# 07_LMS7002M_Power.net
KiCad netlist of a schematic drawn in Altium Designer
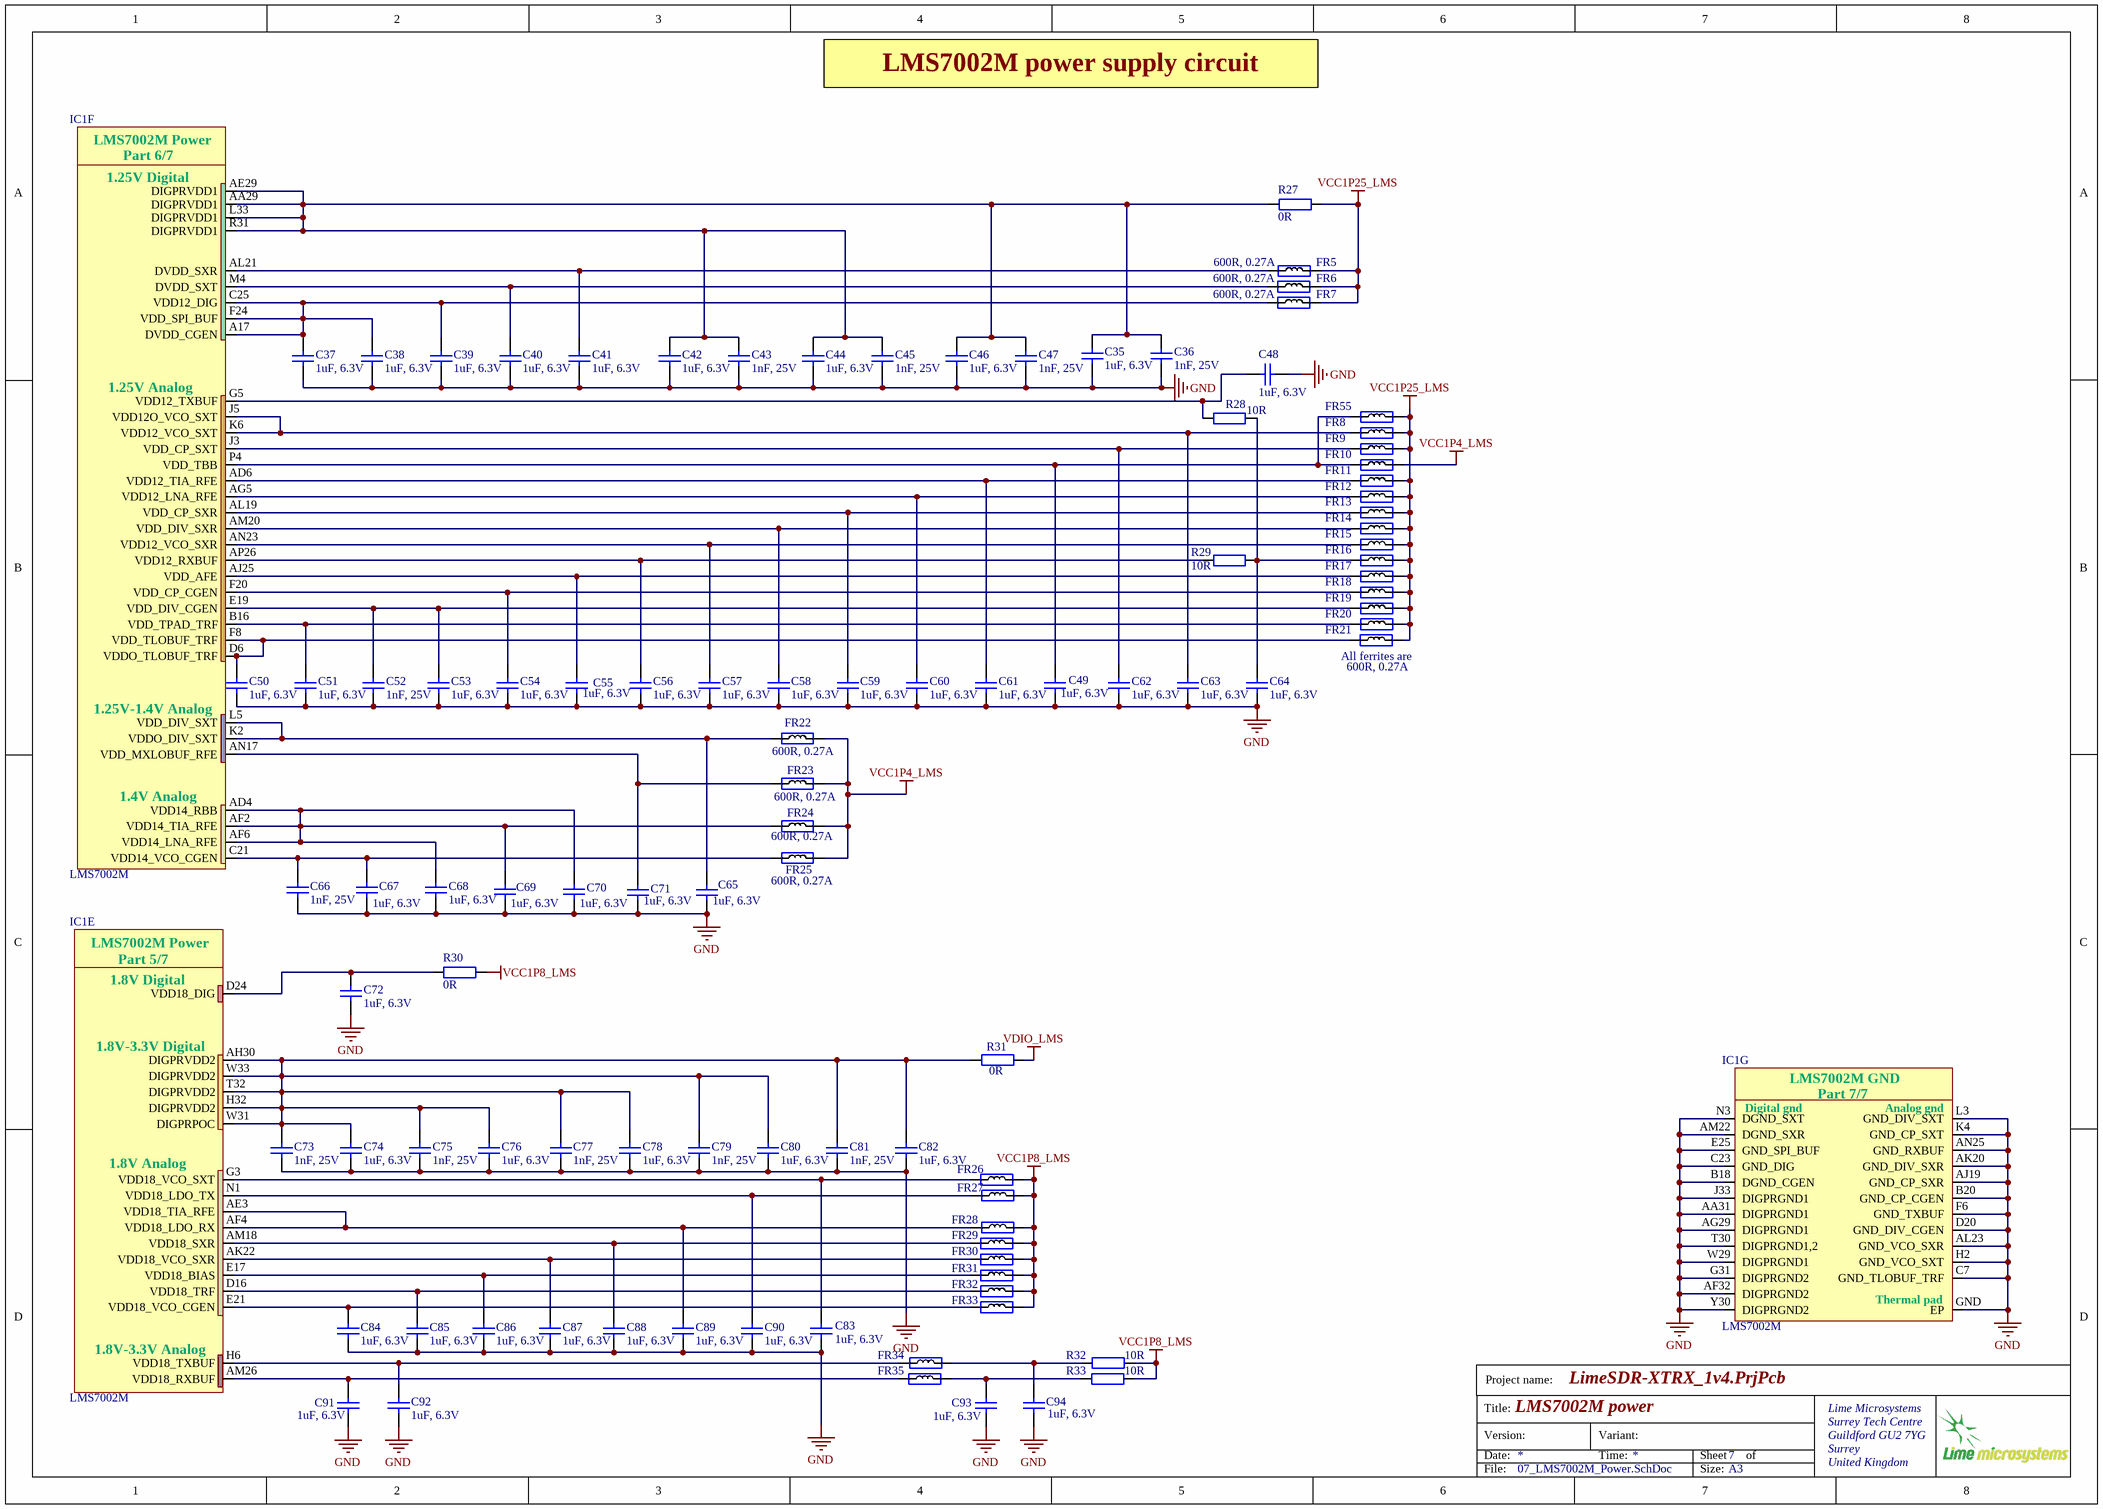
[diagram p0: 07_LMS7002M_Power.SchDoc]

(export (version "E")
  (design (tool "Eeschema 10.0.6"))
  (components
    (comp (ref "C35")
      (value "1uF, 6.3V")
      (footprint "CAP0201")
      (fields (field (name "TOLERANCE") "±20%") (field (name "MANUFACTURER") "TDK Corporation"))
      (libsource (lib "LimeMicroAltiumLib_schLib") (part "Cap_0402"))
    )
    (comp (ref "C36")
      (value "1nF, 25V")
      (footprint "CAP0201")
      (fields (field (name "TOLERANCE") "±10%") (field (name "MANUFACTURER") "TDK Corporation"))
      (libsource (lib "LimeMicroAltiumLib_schLib") (part "Cap_0402"))
    )
    (comp (ref "C37")
      (value "1uF, 6.3V")
      (footprint "CAP0201")
      (fields (field (name "TOLERANCE") "±20%") (field (name "MANUFACTURER") "TDK Corporation"))
      (libsource (lib "LimeMicroAltiumLib_schLib") (part "Cap_0402"))
    )
    (comp (ref "C38")
      (value "1uF, 6.3V")
      (footprint "CAP0201")
      (fields (field (name "TOLERANCE") "±20%") (field (name "MANUFACTURER") "TDK Corporation"))
      (libsource (lib "LimeMicroAltiumLib_schLib") (part "Cap_0402"))
    )
    (comp (ref "C39")
      (value "1uF, 6.3V")
      (footprint "CAP0201")
      (fields (field (name "TOLERANCE") "±20%") (field (name "MANUFACTURER") "TDK Corporation"))
      (libsource (lib "LimeMicroAltiumLib_schLib") (part "Cap_0402"))
    )
    (comp (ref "C40")
      (value "1uF, 6.3V")
      (footprint "CAP0201")
      (fields (field (name "TOLERANCE") "±20%") (field (name "MANUFACTURER") "TDK Corporation"))
      (libsource (lib "LimeMicroAltiumLib_schLib") (part "Cap_0402"))
    )
    (comp (ref "C41")
      (value "1uF, 6.3V")
      (footprint "CAP0201")
      (fields (field (name "TOLERANCE") "±20%") (field (name "MANUFACTURER") "TDK Corporation"))
      (libsource (lib "LimeMicroAltiumLib_schLib") (part "Cap_0402"))
    )
    (comp (ref "C42")
      (value "1uF, 6.3V")
      (footprint "CAP0201")
      (fields (field (name "TOLERANCE") "±20%") (field (name "MANUFACTURER") "TDK Corporation"))
      (libsource (lib "LimeMicroAltiumLib_schLib") (part "Cap_0402"))
    )
    (comp (ref "C43")
      (value "1nF, 25V")
      (footprint "CAP0201")
      (fields (field (name "TOLERANCE") "±10%") (field (name "MANUFACTURER") "TDK Corporation"))
      (libsource (lib "LimeMicroAltiumLib_schLib") (part "Cap_0402"))
    )
    (comp (ref "C44")
      (value "1uF, 6.3V")
      (footprint "CAP0201")
      (fields (field (name "TOLERANCE") "±20%") (field (name "MANUFACTURER") "TDK Corporation"))
      (libsource (lib "LimeMicroAltiumLib_schLib") (part "Cap_0402"))
    )
    (comp (ref "C45")
      (value "1nF, 25V")
      (footprint "CAP0201")
      (fields (field (name "TOLERANCE") "±10%") (field (name "MANUFACTURER") "TDK Corporation"))
      (libsource (lib "LimeMicroAltiumLib_schLib") (part "Cap_0402"))
    )
    (comp (ref "C46")
      (value "1uF, 6.3V")
      (footprint "CAP0201")
      (fields (field (name "TOLERANCE") "±20%") (field (name "MANUFACTURER") "TDK Corporation"))
      (libsource (lib "LimeMicroAltiumLib_schLib") (part "Cap_0402"))
    )
    (comp (ref "C47")
      (value "1nF, 25V")
      (footprint "CAP0201")
      (fields (field (name "TOLERANCE") "±10%") (field (name "MANUFACTURER") "TDK Corporation"))
      (libsource (lib "LimeMicroAltiumLib_schLib") (part "Cap_0402"))
    )
    (comp (ref "C48")
      (value "1uF, 6.3V")
      (footprint "CAP0201")
      (fields (field (name "TOLERANCE") "±20%") (field (name "MANUFACTURER") "TDK Corporation"))
      (libsource (lib "LimeMicroAltiumLib_schLib") (part "Cap_0402"))
    )
    (comp (ref "C49")
      (value "1uF, 6.3V")
      (footprint "CAP0201")
      (fields (field (name "TOLERANCE") "±20%") (field (name "MANUFACTURER") "TDK Corporation"))
      (libsource (lib "LimeMicroAltiumLib_schLib") (part "Cap_0402"))
    )
    (comp (ref "C50")
      (value "1uF, 6.3V")
      (footprint "CAP0201")
      (fields (field (name "TOLERANCE") "±20%") (field (name "MANUFACTURER") "TDK Corporation"))
      (libsource (lib "LimeMicroAltiumLib_schLib") (part "Cap_0402"))
    )
    (comp (ref "C51")
      (value "1uF, 6.3V")
      (footprint "CAP0201")
      (fields (field (name "TOLERANCE") "±20%") (field (name "MANUFACTURER") "TDK Corporation"))
      (libsource (lib "LimeMicroAltiumLib_schLib") (part "Cap_0402"))
    )
    (comp (ref "C52")
      (value "1nF, 25V")
      (footprint "CAP0201")
      (fields (field (name "TOLERANCE") "±10%") (field (name "MANUFACTURER") "TDK Corporation"))
      (libsource (lib "LimeMicroAltiumLib_schLib") (part "Cap_0402"))
    )
    (comp (ref "C53")
      (value "1uF, 6.3V")
      (footprint "CAP0201")
      (fields (field (name "TOLERANCE") "±20%") (field (name "MANUFACTURER") "TDK Corporation"))
      (libsource (lib "LimeMicroAltiumLib_schLib") (part "Cap_0402"))
    )
    (comp (ref "C54")
      (value "1uF, 6.3V")
      (footprint "CAP0201")
      (fields (field (name "TOLERANCE") "±20%") (field (name "MANUFACTURER") "TDK Corporation"))
      (libsource (lib "LimeMicroAltiumLib_schLib") (part "Cap_0402"))
    )
    (comp (ref "C55")
      (value "1uF, 6.3V")
      (footprint "CAP0201")
      (fields (field (name "TOLERANCE") "±20%") (field (name "MANUFACTURER") "TDK Corporation"))
      (libsource (lib "LimeMicroAltiumLib_schLib") (part "Cap_0402"))
    )
    (comp (ref "C56")
      (value "1uF, 6.3V")
      (footprint "CAP0201")
      (fields (field (name "TOLERANCE") "±20%") (field (name "MANUFACTURER") "TDK Corporation"))
      (libsource (lib "LimeMicroAltiumLib_schLib") (part "Cap_0402"))
    )
    (comp (ref "C57")
      (value "1uF, 6.3V")
      (footprint "CAP0201")
      (fields (field (name "TOLERANCE") "±20%") (field (name "MANUFACTURER") "TDK Corporation"))
      (libsource (lib "LimeMicroAltiumLib_schLib") (part "Cap_0402"))
    )
    (comp (ref "C58")
      (value "1uF, 6.3V")
      (footprint "CAP0201")
      (fields (field (name "TOLERANCE") "±20%") (field (name "MANUFACTURER") "TDK Corporation"))
      (libsource (lib "LimeMicroAltiumLib_schLib") (part "Cap_0402"))
    )
    (comp (ref "C59")
      (value "1uF, 6.3V")
      (footprint "CAP0201")
      (fields (field (name "TOLERANCE") "±20%") (field (name "MANUFACTURER") "TDK Corporation"))
      (libsource (lib "LimeMicroAltiumLib_schLib") (part "Cap_0402"))
    )
    (comp (ref "C60")
      (value "1uF, 6.3V")
      (footprint "CAP0201")
      (fields (field (name "TOLERANCE") "±20%") (field (name "MANUFACTURER") "TDK Corporation"))
      (libsource (lib "LimeMicroAltiumLib_schLib") (part "Cap_0402"))
    )
    (comp (ref "C61")
      (value "1uF, 6.3V")
      (footprint "CAP0201")
      (fields (field (name "TOLERANCE") "±20%") (field (name "MANUFACTURER") "TDK Corporation"))
      (libsource (lib "LimeMicroAltiumLib_schLib") (part "Cap_0402"))
    )
    (comp (ref "C62")
      (value "1uF, 6.3V")
      (footprint "CAP0201")
      (fields (field (name "TOLERANCE") "±20%") (field (name "MANUFACTURER") "TDK Corporation"))
      (libsource (lib "LimeMicroAltiumLib_schLib") (part "Cap_0402"))
    )
    (comp (ref "C63")
      (value "1uF, 6.3V")
      (footprint "CAP0201")
      (fields (field (name "TOLERANCE") "±20%") (field (name "MANUFACTURER") "TDK Corporation"))
      (libsource (lib "LimeMicroAltiumLib_schLib") (part "Cap_0402"))
    )
    (comp (ref "C64")
      (value "1uF, 6.3V")
      (footprint "CAP0201")
      (fields (field (name "TOLERANCE") "±20%") (field (name "MANUFACTURER") "TDK Corporation"))
      (libsource (lib "LimeMicroAltiumLib_schLib") (part "Cap_0402"))
    )
    (comp (ref "C65")
      (value "1uF, 6.3V")
      (footprint "CAP0201")
      (fields (field (name "TOLERANCE") "±20%") (field (name "MANUFACTURER") "TDK Corporation"))
      (libsource (lib "LimeMicroAltiumLib_schLib") (part "Cap_0402"))
    )
    (comp (ref "C66")
      (value "1nF, 25V")
      (footprint "CAP0201")
      (fields (field (name "TOLERANCE") "±10%") (field (name "MANUFACTURER") "TDK Corporation"))
      (libsource (lib "LimeMicroAltiumLib_schLib") (part "Cap_0402"))
    )
    (comp (ref "C67")
      (value "1uF, 6.3V")
      (footprint "CAP0201")
      (fields (field (name "TOLERANCE") "±20%") (field (name "MANUFACTURER") "TDK Corporation"))
      (libsource (lib "LimeMicroAltiumLib_schLib") (part "Cap_0402"))
    )
    (comp (ref "C68")
      (value "1uF, 6.3V")
      (footprint "CAP0201")
      (fields (field (name "TOLERANCE") "±20%") (field (name "MANUFACTURER") "TDK Corporation"))
      (libsource (lib "LimeMicroAltiumLib_schLib") (part "Cap_0402"))
    )
    (comp (ref "C69")
      (value "1uF, 6.3V")
      (footprint "CAP0201")
      (fields (field (name "TOLERANCE") "±20%") (field (name "MANUFACTURER") "TDK Corporation"))
      (libsource (lib "LimeMicroAltiumLib_schLib") (part "Cap_0402"))
    )
    (comp (ref "C70")
      (value "1uF, 6.3V")
      (footprint "CAP0201")
      (fields (field (name "TOLERANCE") "±20%") (field (name "MANUFACTURER") "TDK Corporation"))
      (libsource (lib "LimeMicroAltiumLib_schLib") (part "Cap_0402"))
    )
    (comp (ref "C71")
      (value "1uF, 6.3V")
      (footprint "CAP0201")
      (fields (field (name "TOLERANCE") "±20%") (field (name "MANUFACTURER") "TDK Corporation"))
      (libsource (lib "LimeMicroAltiumLib_schLib") (part "Cap_0402"))
    )
    (comp (ref "C72")
      (value "1uF, 6.3V")
      (footprint "CAP0201")
      (fields (field (name "TOLERANCE") "±20%") (field (name "MANUFACTURER") "TDK Corporation"))
      (libsource (lib "LimeMicroAltiumLib_schLib") (part "Cap_0402"))
    )
    (comp (ref "C73")
      (value "1nF, 25V")
      (footprint "CAP0201")
      (fields (field (name "TOLERANCE") "±10%") (field (name "MANUFACTURER") "TDK Corporation"))
      (libsource (lib "LimeMicroAltiumLib_schLib") (part "Cap_0402"))
    )
    (comp (ref "C74")
      (value "1uF, 6.3V")
      (footprint "CAP0201")
      (fields (field (name "TOLERANCE") "±20%") (field (name "MANUFACTURER") "TDK Corporation"))
      (libsource (lib "LimeMicroAltiumLib_schLib") (part "Cap_0402"))
    )
    (comp (ref "C75")
      (value "1nF, 25V")
      (footprint "CAP0201")
      (fields (field (name "TOLERANCE") "±10%") (field (name "MANUFACTURER") "TDK Corporation"))
      (libsource (lib "LimeMicroAltiumLib_schLib") (part "Cap_0402"))
    )
    (comp (ref "C76")
      (value "1uF, 6.3V")
      (footprint "CAP0201")
      (fields (field (name "TOLERANCE") "±20%") (field (name "MANUFACTURER") "TDK Corporation"))
      (libsource (lib "LimeMicroAltiumLib_schLib") (part "Cap_0402"))
    )
    (comp (ref "C77")
      (value "1nF, 25V")
      (footprint "CAP0201")
      (fields (field (name "TOLERANCE") "±10%") (field (name "MANUFACTURER") "TDK Corporation"))
      (libsource (lib "LimeMicroAltiumLib_schLib") (part "Cap_0402"))
    )
    (comp (ref "C78")
      (value "1uF, 6.3V")
      (footprint "CAP0201")
      (fields (field (name "TOLERANCE") "±20%") (field (name "MANUFACTURER") "TDK Corporation"))
      (libsource (lib "LimeMicroAltiumLib_schLib") (part "Cap_0402"))
    )
    (comp (ref "C79")
      (value "1nF, 25V")
      (footprint "CAP0201")
      (fields (field (name "TOLERANCE") "±10%") (field (name "MANUFACTURER") "TDK Corporation"))
      (libsource (lib "LimeMicroAltiumLib_schLib") (part "Cap_0402"))
    )
    (comp (ref "C80")
      (value "1uF, 6.3V")
      (footprint "CAP0201")
      (fields (field (name "TOLERANCE") "±20%") (field (name "MANUFACTURER") "TDK Corporation"))
      (libsource (lib "LimeMicroAltiumLib_schLib") (part "Cap_0402"))
    )
    (comp (ref "C81")
      (value "1nF, 25V")
      (footprint "CAP0201")
      (fields (field (name "TOLERANCE") "±10%") (field (name "MANUFACTURER") "TDK Corporation"))
      (libsource (lib "LimeMicroAltiumLib_schLib") (part "Cap_0402"))
    )
    (comp (ref "C82")
      (value "1uF, 6.3V")
      (footprint "CAP0201")
      (fields (field (name "TOLERANCE") "±20%") (field (name "MANUFACTURER") "TDK Corporation"))
      (libsource (lib "LimeMicroAltiumLib_schLib") (part "Cap_0402"))
    )
    (comp (ref "C83")
      (value "1uF, 6.3V")
      (footprint "CAP0201")
      (fields (field (name "TOLERANCE") "±20%") (field (name "MANUFACTURER") "TDK Corporation"))
      (libsource (lib "LimeMicroAltiumLib_schLib") (part "Cap_0402"))
    )
    (comp (ref "C84")
      (value "1uF, 6.3V")
      (footprint "CAP0201")
      (fields (field (name "TOLERANCE") "±20%") (field (name "MANUFACTURER") "TDK Corporation"))
      (libsource (lib "LimeMicroAltiumLib_schLib") (part "Cap_0402"))
    )
    (comp (ref "C85")
      (value "1uF, 6.3V")
      (footprint "CAP0201")
      (fields (field (name "TOLERANCE") "±20%") (field (name "MANUFACTURER") "TDK Corporation"))
      (libsource (lib "LimeMicroAltiumLib_schLib") (part "Cap_0402"))
    )
    (comp (ref "C86")
      (value "1uF, 6.3V")
      (footprint "CAP0201")
      (fields (field (name "TOLERANCE") "±20%") (field (name "MANUFACTURER") "TDK Corporation"))
      (libsource (lib "LimeMicroAltiumLib_schLib") (part "Cap_0402"))
    )
    (comp (ref "C87")
      (value "1uF, 6.3V")
      (footprint "CAP0201")
      (fields (field (name "TOLERANCE") "±20%") (field (name "MANUFACTURER") "TDK Corporation"))
      (libsource (lib "LimeMicroAltiumLib_schLib") (part "Cap_0402"))
    )
    (comp (ref "C88")
      (value "1uF, 6.3V")
      (footprint "CAP0201")
      (fields (field (name "TOLERANCE") "±20%") (field (name "MANUFACTURER") "TDK Corporation"))
      (libsource (lib "LimeMicroAltiumLib_schLib") (part "Cap_0402"))
    )
    (comp (ref "C89")
      (value "1uF, 6.3V")
      (footprint "CAP0201")
      (fields (field (name "TOLERANCE") "±20%") (field (name "MANUFACTURER") "TDK Corporation"))
      (libsource (lib "LimeMicroAltiumLib_schLib") (part "Cap_0402"))
    )
    (comp (ref "C90")
      (value "1uF, 6.3V")
      (footprint "CAP0201")
      (fields (field (name "TOLERANCE") "±20%") (field (name "MANUFACTURER") "TDK Corporation"))
      (libsource (lib "LimeMicroAltiumLib_schLib") (part "Cap_0402"))
    )
    (comp (ref "C91")
      (value "1uF, 6.3V")
      (footprint "CAP0201")
      (fields (field (name "TOLERANCE") "±20%") (field (name "MANUFACTURER") "TDK Corporation"))
      (libsource (lib "LimeMicroAltiumLib_schLib") (part "Cap_0402"))
    )
    (comp (ref "C92")
      (value "1uF, 6.3V")
      (footprint "CAP0201")
      (fields (field (name "TOLERANCE") "±20%") (field (name "MANUFACTURER") "TDK Corporation"))
      (libsource (lib "LimeMicroAltiumLib_schLib") (part "Cap_0402"))
    )
    (comp (ref "C93")
      (value "1uF, 6.3V")
      (footprint "CAP0201")
      (fields (field (name "TOLERANCE") "±20%") (field (name "MANUFACTURER") "TDK Corporation"))
      (libsource (lib "LimeMicroAltiumLib_schLib") (part "Cap_0402"))
    )
    (comp (ref "C94")
      (value "1uF, 6.3V")
      (footprint "CAP0201")
      (fields (field (name "TOLERANCE") "±20%") (field (name "MANUFACTURER") "TDK Corporation"))
      (libsource (lib "LimeMicroAltiumLib_schLib") (part "Cap_0402"))
    )
    (comp (ref "FR5")
      (value "600R, 0.27A")
      (footprint "RES0201")
      (fields (field (name "MANUFACTURER") "Taiyo Yuden"))
      (libsource (lib "LimeMicroAltiumLib_schLib") (part "Ferrite"))
    )
    (comp (ref "FR6")
      (value "600R, 0.27A")
      (footprint "RES0201")
      (fields (field (name "MANUFACTURER") "Taiyo Yuden"))
      (libsource (lib "LimeMicroAltiumLib_schLib") (part "Ferrite"))
    )
    (comp (ref "FR7")
      (value "600R, 0.27A")
      (footprint "RES0201")
      (fields (field (name "MANUFACTURER") "Taiyo Yuden"))
      (libsource (lib "LimeMicroAltiumLib_schLib") (part "Ferrite"))
    )
    (comp (ref "FR8")
      (value "600R, 0.27A")
      (footprint "RES0201")
      (fields (field (name "MANUFACTURER") "Taiyo Yuden"))
      (libsource (lib "LimeMicroAltiumLib_schLib") (part "Ferrite"))
    )
    (comp (ref "FR9")
      (value "600R, 0.27A")
      (footprint "RES0201")
      (fields (field (name "MANUFACTURER") "Taiyo Yuden"))
      (libsource (lib "LimeMicroAltiumLib_schLib") (part "Ferrite"))
    )
    (comp (ref "FR10")
      (value "600R, 0.27A")
      (footprint "RES0201")
      (fields (field (name "MANUFACTURER") "Taiyo Yuden"))
      (libsource (lib "LimeMicroAltiumLib_schLib") (part "Ferrite"))
    )
    (comp (ref "FR11")
      (value "600R, 0.27A")
      (footprint "RES0201")
      (fields (field (name "MANUFACTURER") "Taiyo Yuden"))
      (libsource (lib "LimeMicroAltiumLib_schLib") (part "Ferrite"))
    )
    (comp (ref "FR12")
      (value "600R, 0.27A")
      (footprint "RES0201")
      (fields (field (name "MANUFACTURER") "Taiyo Yuden"))
      (libsource (lib "LimeMicroAltiumLib_schLib") (part "Ferrite"))
    )
    (comp (ref "FR13")
      (value "600R, 0.27A")
      (footprint "RES0201")
      (fields (field (name "MANUFACTURER") "Taiyo Yuden"))
      (libsource (lib "LimeMicroAltiumLib_schLib") (part "Ferrite"))
    )
    (comp (ref "FR14")
      (value "600R, 0.27A")
      (footprint "RES0201")
      (fields (field (name "MANUFACTURER") "Taiyo Yuden"))
      (libsource (lib "LimeMicroAltiumLib_schLib") (part "Ferrite"))
    )
    (comp (ref "FR15")
      (value "600R, 0.27A")
      (footprint "RES0201")
      (fields (field (name "MANUFACTURER") "Taiyo Yuden"))
      (libsource (lib "LimeMicroAltiumLib_schLib") (part "Ferrite"))
    )
    (comp (ref "FR16")
      (value "600R, 0.27A")
      (footprint "RES0201")
      (fields (field (name "MANUFACTURER") "Taiyo Yuden"))
      (libsource (lib "LimeMicroAltiumLib_schLib") (part "Ferrite"))
    )
    (comp (ref "FR17")
      (value "600R, 0.27A")
      (footprint "RES0201")
      (fields (field (name "MANUFACTURER") "Taiyo Yuden"))
      (libsource (lib "LimeMicroAltiumLib_schLib") (part "Ferrite"))
    )
    (comp (ref "FR18")
      (value "600R, 0.27A")
      (footprint "RES0201")
      (fields (field (name "MANUFACTURER") "Taiyo Yuden"))
      (libsource (lib "LimeMicroAltiumLib_schLib") (part "Ferrite"))
    )
    (comp (ref "FR19")
      (value "600R, 0.27A")
      (footprint "RES0201")
      (fields (field (name "MANUFACTURER") "Taiyo Yuden"))
      (libsource (lib "LimeMicroAltiumLib_schLib") (part "Ferrite"))
    )
    (comp (ref "FR20")
      (value "600R, 0.27A")
      (footprint "RES0201")
      (fields (field (name "MANUFACTURER") "Taiyo Yuden"))
      (libsource (lib "LimeMicroAltiumLib_schLib") (part "Ferrite"))
    )
    (comp (ref "FR21")
      (value "600R, 0.27A")
      (footprint "RES0201")
      (fields (field (name "MANUFACTURER") "Taiyo Yuden"))
      (libsource (lib "LimeMicroAltiumLib_schLib") (part "Ferrite"))
    )
    (comp (ref "FR22")
      (value "600R, 0.27A")
      (footprint "RES0201")
      (fields (field (name "MANUFACTURER") "Taiyo Yuden"))
      (libsource (lib "LimeMicroAltiumLib_schLib") (part "Ferrite"))
    )
    (comp (ref "FR23")
      (value "600R, 0.27A")
      (footprint "RES0201")
      (fields (field (name "MANUFACTURER") "Taiyo Yuden"))
      (libsource (lib "LimeMicroAltiumLib_schLib") (part "Ferrite"))
    )
    (comp (ref "FR24")
      (value "600R, 0.27A")
      (footprint "RES0201")
      (fields (field (name "MANUFACTURER") "Taiyo Yuden"))
      (libsource (lib "LimeMicroAltiumLib_schLib") (part "Ferrite"))
    )
    (comp (ref "FR25")
      (value "600R, 0.27A")
      (footprint "RES0201")
      (fields (field (name "MANUFACTURER") "Taiyo Yuden"))
      (libsource (lib "LimeMicroAltiumLib_schLib") (part "Ferrite"))
    )
    (comp (ref "FR26")
      (value "600R, 0.27A")
      (footprint "RES0201")
      (fields (field (name "MANUFACTURER") "Taiyo Yuden"))
      (libsource (lib "LimeMicroAltiumLib_schLib") (part "Ferrite"))
    )
    (comp (ref "FR27")
      (value "600R, 0.27A")
      (footprint "RES0201")
      (fields (field (name "MANUFACTURER") "Taiyo Yuden"))
      (libsource (lib "") (part "Ferrite_1"))
    )
    (comp (ref "FR28")
      (value "600R, 0.27A")
      (footprint "RES0201")
      (fields (field (name "MANUFACTURER") "Taiyo Yuden"))
      (libsource (lib "") (part "Ferrite_1"))
    )
    (comp (ref "FR29")
      (value "600R, 0.27A")
      (footprint "RES0201")
      (fields (field (name "MANUFACTURER") "Taiyo Yuden"))
      (libsource (lib "LimeMicroAltiumLib_schLib") (part "Ferrite"))
    )
    (comp (ref "FR30")
      (value "600R, 0.27A")
      (footprint "RES0201")
      (fields (field (name "MANUFACTURER") "Taiyo Yuden"))
      (libsource (lib "LimeMicroAltiumLib_schLib") (part "Ferrite"))
    )
    (comp (ref "FR31")
      (value "600R, 0.27A")
      (footprint "RES0201")
      (fields (field (name "MANUFACTURER") "Taiyo Yuden"))
      (libsource (lib "LimeMicroAltiumLib_schLib") (part "Ferrite"))
    )
    (comp (ref "FR32")
      (value "600R, 0.27A")
      (footprint "RES0201")
      (fields (field (name "MANUFACTURER") "Taiyo Yuden"))
      (libsource (lib "LimeMicroAltiumLib_schLib") (part "Ferrite"))
    )
    (comp (ref "FR33")
      (value "600R, 0.27A")
      (footprint "RES0201")
      (fields (field (name "MANUFACTURER") "Taiyo Yuden"))
      (libsource (lib "LimeMicroAltiumLib_schLib") (part "Ferrite"))
    )
    (comp (ref "FR34")
      (value "600R, 0.27A")
      (footprint "RES0201")
      (fields (field (name "MANUFACTURER") "Taiyo Yuden"))
      (libsource (lib "") (part "Ferrite_1"))
    )
    (comp (ref "FR35")
      (value "600R, 0.27A")
      (footprint "RES0201")
      (fields (field (name "MANUFACTURER") "Taiyo Yuden"))
      (libsource (lib "LimeMicroAltiumLib_schLib") (part "Ferrite"))
    )
    (comp (ref "FR55")
      (value "600R, 0.27A")
      (footprint "RES0201")
      (fields (field (name "MANUFACTURER") "Taiyo Yuden"))
      (libsource (lib "LimeMicroAltiumLib_schLib") (part "Ferrite"))
    )
    (comp (ref "IC1")
      (value "LMS7002M")
      (footprint "LMS7002M_v5_LESS_SILK")
      (description "Schematic symbol revision 4. Default footprint - 0.31mm pad")
      (fields (field (name "MANUFACTURER") "Lime Microsystems"))
      (libsource (lib "LimeMicroAltiumLib_schLib_r04") (part "LMS7002Mr4"))
    )
    (comp (ref "R27")
      (value "0R")
      (footprint "RES0402")
      (fields (field (name "MANUFACTURER") "Yageo") (field (name "TOLERANCE") "Jumper"))
      (libsource (lib "LimeMicroAltiumLib_schLib") (part "Res_0402"))
    )
    (comp (ref "R28")
      (value "10R")
      (footprint "RES0201")
      (fields
        (field (name "MANUFACTURER") "Panasonic Electronic Components")
        (field (name "TOLERANCE") "±1%")
      )
      (libsource (lib "LimeMicroAltiumLib_schLib") (part "Res_0402"))
    )
    (comp (ref "R29")
      (value "10R")
      (footprint "RES0201")
      (fields
        (field (name "MANUFACTURER") "Panasonic Electronic Components")
        (field (name "TOLERANCE") "±1%")
      )
      (libsource (lib "LimeMicroAltiumLib_schLib") (part "Res_0402"))
    )
    (comp (ref "R30")
      (value "0R")
      (footprint "RES0201")
      (fields (field (name "MANUFACTURER") "Yageo") (field (name "TOLERANCE") "5%"))
      (libsource (lib "LimeMicroAltiumLib_schLib") (part "Res_0402"))
    )
    (comp (ref "R31")
      (value "0R")
      (footprint "RES0402")
      (fields (field (name "MANUFACTURER") "Yageo") (field (name "TOLERANCE") "Jumper"))
      (libsource (lib "LimeMicroAltiumLib_schLib") (part "Res_0402"))
    )
    (comp (ref "R32")
      (value "10R")
      (footprint "RES0201")
      (fields
        (field (name "MANUFACTURER") "Panasonic Electronic Components")
        (field (name "TOLERANCE") "±1%")
      )
      (libsource (lib "LimeMicroAltiumLib_schLib") (part "Res_0402"))
    )
    (comp (ref "R33")
      (value "10R")
      (footprint "RES0201")
      (fields
        (field (name "MANUFACTURER") "Panasonic Electronic Components")
        (field (name "TOLERANCE") "±1%")
      )
      (libsource (lib "LimeMicroAltiumLib_schLib") (part "Res_0402"))
    )
  )
  (nets
    (net (code "1") (name "GND") (class "Default")
      (node (ref "C35") (pin "2") (pinfunction "2_2") (pintype "passive"))
      (node (ref "C36") (pin "2") (pinfunction "2_2") (pintype "passive"))
      (node (ref "C37") (pin "2") (pinfunction "2_2") (pintype "passive"))
      (node (ref "C38") (pin "2") (pinfunction "2_2") (pintype "passive"))
      (node (ref "C39") (pin "2") (pinfunction "2_2") (pintype "passive"))
      (node (ref "C40") (pin "1") (pinfunction "1_1") (pintype "passive"))
      (node (ref "C41") (pin "2") (pinfunction "2_2") (pintype "passive"))
      (node (ref "C42") (pin "2") (pinfunction "2_2") (pintype "passive"))
      (node (ref "C43") (pin "2") (pinfunction "2_2") (pintype "passive"))
      (node (ref "C44") (pin "2") (pinfunction "2_2") (pintype "passive"))
      (node (ref "C45") (pin "2") (pinfunction "2_2") (pintype "passive"))
      (node (ref "C46") (pin "2") (pinfunction "2_2") (pintype "passive"))
      (node (ref "C47") (pin "2") (pinfunction "2_2") (pintype "passive"))
      (node (ref "C48") (pin "2") (pinfunction "2_2") (pintype "passive"))
      (node (ref "C49") (pin "2") (pinfunction "2_2") (pintype "passive"))
      (node (ref "C50") (pin "2") (pinfunction "2_2") (pintype "passive"))
      (node (ref "C51") (pin "2") (pinfunction "2_2") (pintype "passive"))
      (node (ref "C52") (pin "2") (pinfunction "2_2") (pintype "passive"))
      (node (ref "C53") (pin "2") (pinfunction "2_2") (pintype "passive"))
      (node (ref "C54") (pin "1") (pinfunction "1_1") (pintype "passive"))
      (node (ref "C55") (pin "2") (pinfunction "2_2") (pintype "passive"))
      (node (ref "C56") (pin "2") (pinfunction "2_2") (pintype "passive"))
      (node (ref "C57") (pin "2") (pinfunction "2_2") (pintype "passive"))
      (node (ref "C58") (pin "2") (pinfunction "2_2") (pintype "passive"))
      (node (ref "C59") (pin "2") (pinfunction "2_2") (pintype "passive"))
      (node (ref "C60") (pin "2") (pinfunction "2_2") (pintype "passive"))
      (node (ref "C61") (pin "1") (pinfunction "1_1") (pintype "passive"))
      (node (ref "C62") (pin "2") (pinfunction "2_2") (pintype "passive"))
      (node (ref "C63") (pin "1") (pinfunction "1_1") (pintype "passive"))
      (node (ref "C64") (pin "1") (pinfunction "1_1") (pintype "passive"))
      (node (ref "C65") (pin "2") (pinfunction "2_2") (pintype "passive"))
      (node (ref "C66") (pin "2") (pinfunction "2_2") (pintype "passive"))
      (node (ref "C67") (pin "2") (pinfunction "2_2") (pintype "passive"))
      (node (ref "C68") (pin "2") (pinfunction "2_2") (pintype "passive"))
      (node (ref "C69") (pin "2") (pinfunction "2_2") (pintype "passive"))
      (node (ref "C70") (pin "2") (pinfunction "2_2") (pintype "passive"))
      (node (ref "C71") (pin "2") (pinfunction "2_2") (pintype "passive"))
      (node (ref "C72") (pin "2") (pinfunction "2_2") (pintype "passive"))
      (node (ref "C73") (pin "2") (pinfunction "2_2") (pintype "passive"))
      (node (ref "C74") (pin "2") (pinfunction "2_2") (pintype "passive"))
      (node (ref "C75") (pin "2") (pinfunction "2_2") (pintype "passive"))
      (node (ref "C76") (pin "2") (pinfunction "2_2") (pintype "passive"))
      (node (ref "C77") (pin "2") (pinfunction "2_2") (pintype "passive"))
      (node (ref "C78") (pin "2") (pinfunction "2_2") (pintype "passive"))
      (node (ref "C79") (pin "2") (pinfunction "2_2") (pintype "passive"))
      (node (ref "C80") (pin "2") (pinfunction "2_2") (pintype "passive"))
      (node (ref "C81") (pin "2") (pinfunction "2_2") (pintype "passive"))
      (node (ref "C82") (pin "2") (pinfunction "2_2") (pintype "passive"))
      (node (ref "C83") (pin "2") (pinfunction "2_2") (pintype "passive"))
      (node (ref "C84") (pin "2") (pinfunction "2_2") (pintype "passive"))
      (node (ref "C85") (pin "2") (pinfunction "2_2") (pintype "passive"))
      (node (ref "C86") (pin "2") (pinfunction "2_2") (pintype "passive"))
      (node (ref "C87") (pin "2") (pinfunction "2_2") (pintype "passive"))
      (node (ref "C88") (pin "2") (pinfunction "2_2") (pintype "passive"))
      (node (ref "C89") (pin "2") (pinfunction "2_2") (pintype "passive"))
      (node (ref "C90") (pin "2") (pinfunction "2_2") (pintype "passive"))
      (node (ref "C91") (pin "2") (pinfunction "2_2") (pintype "passive"))
      (node (ref "C92") (pin "2") (pinfunction "2_2") (pintype "passive"))
      (node (ref "C93") (pin "2") (pinfunction "2_2") (pintype "passive"))
      (node (ref "C94") (pin "2") (pinfunction "2_2") (pintype "passive"))
      (node (ref "IC1") (pin "AA31") (pinfunction "DIGPRGND1_AA31") (pintype "passive"))
      (node (ref "IC1") (pin "AF32") (pinfunction "DIGPRGND2_AF32") (pintype "passive"))
      (node (ref "IC1") (pin "AG29") (pinfunction "DIGPRGND1_AG29") (pintype "passive"))
      (node (ref "IC1") (pin "AJ19") (pinfunction "GND_CP_SXR_AJ19") (pintype "passive"))
      (node (ref "IC1") (pin "AK20") (pinfunction "GND_DIV_SXR_AK20") (pintype "passive"))
      (node (ref "IC1") (pin "AL23") (pinfunction "GND_VCO_SXR_AL23") (pintype "passive"))
      (node (ref "IC1") (pin "AM22") (pinfunction "DGND_SXR_AM22") (pintype "passive"))
      (node (ref "IC1") (pin "AN25") (pinfunction "GND_RXBUF_AN25") (pintype "passive"))
      (node (ref "IC1") (pin "B18") (pinfunction "DGND_CGEN_B18") (pintype "passive"))
      (node (ref "IC1") (pin "B20") (pinfunction "GND_CP_CGEN_B20") (pintype "passive"))
      (node (ref "IC1") (pin "C23") (pinfunction "GND_DIG_C23") (pintype "passive"))
      (node (ref "IC1") (pin "C7") (pinfunction "GND_TLOBUF_TRF_C7") (pintype "passive"))
      (node (ref "IC1") (pin "D20") (pinfunction "GND_DIV_CGEN_D20") (pintype "passive"))
      (node (ref "IC1") (pin "E25") (pinfunction "GND_SPI_BUF_E25") (pintype "passive"))
      (node (ref "IC1") (pin "F6") (pinfunction "GND_TXBUF_F6") (pintype "passive"))
      (node (ref "IC1") (pin "G31") (pinfunction "DIGPRGND2_G31") (pintype "passive"))
      (node (ref "IC1") (pin "GND") (pinfunction "EP_GND") (pintype "passive"))
      (node (ref "IC1") (pin "H2") (pinfunction "GND_VCO_SXT_H2") (pintype "passive"))
      (node (ref "IC1") (pin "J33") (pinfunction "DIGPRGND1_J33") (pintype "passive"))
      (node (ref "IC1") (pin "K4") (pinfunction "GND_CP_SXT_K4") (pintype "passive"))
      (node (ref "IC1") (pin "L3") (pinfunction "GND_DIV_SXT_L3") (pintype "passive"))
      (node (ref "IC1") (pin "N3") (pinfunction "DGND_SXT_N3") (pintype "passive"))
      (node (ref "IC1") (pin "T30") (pinfunction "DIGPRGND1,2_T30") (pintype "passive"))
      (node (ref "IC1") (pin "W29") (pinfunction "DIGPRGND1_W29") (pintype "passive"))
      (node (ref "IC1") (pin "Y30") (pinfunction "DIGPRGND2_Y30") (pintype "passive"))
    )
    (net (code "2") (name "Net-(C35-Pad1)") (class "Default")
      (node (ref "C35") (pin "1") (pinfunction "1_1") (pintype "passive"))
      (node (ref "C36") (pin "1") (pinfunction "1_1") (pintype "passive"))
      (node (ref "C42") (pin "1") (pinfunction "1_1") (pintype "passive"))
      (node (ref "C43") (pin "1") (pinfunction "1_1") (pintype "passive"))
      (node (ref "C44") (pin "1") (pinfunction "1_1") (pintype "passive"))
      (node (ref "C45") (pin "1") (pinfunction "1_1") (pintype "passive"))
      (node (ref "C46") (pin "1") (pinfunction "1_1") (pintype "passive"))
      (node (ref "C47") (pin "1") (pinfunction "1_1") (pintype "passive"))
      (node (ref "IC1") (pin "AA29") (pinfunction "DIGPRVDD1_AA29") (pintype "power_in"))
      (node (ref "IC1") (pin "AE29") (pinfunction "DIGPRVDD1_AE29") (pintype "power_in"))
      (node (ref "IC1") (pin "L33") (pinfunction "DIGPRVDD1_L33") (pintype "power_in"))
      (node (ref "IC1") (pin "R31") (pinfunction "DIGPRVDD1_R31") (pintype "power_in"))
      (node (ref "R27") (pin "2") (pinfunction "2_2") (pintype "passive"))
    )
    (net (code "3") (name "Net-(C64-Pad2)") (class "Default")
      (node (ref "C64") (pin "2") (pinfunction "2_2") (pintype "passive"))
      (node (ref "FR16") (pin "1") (pinfunction "1_1") (pintype "passive"))
      (node (ref "R28") (pin "2") (pinfunction "2_2") (pintype "passive"))
      (node (ref "R29") (pin "2") (pinfunction "2_2") (pintype "passive"))
    )
    (net (code "4") (name "Net-(C93-Pad1)") (class "Default")
      (node (ref "C93") (pin "1") (pinfunction "1_1") (pintype "passive"))
      (node (ref "FR35") (pin "2") (pinfunction "2_2") (pintype "passive"))
      (node (ref "R33") (pin "2") (pinfunction "2_2") (pintype "passive"))
    )
    (net (code "5") (name "Net-(C94-Pad1)") (class "Default")
      (node (ref "C94") (pin "1") (pinfunction "1_1") (pintype "passive"))
      (node (ref "FR34") (pin "1") (pinfunction "1_1") (pintype "passive"))
      (node (ref "R32") (pin "1") (pinfunction "1_1") (pintype "passive"))
    )
    (net (code "6") (name "Net-(IC1E-DIGPRPOC)") (class "Default")
      (node (ref "C73") (pin "1") (pinfunction "1_1") (pintype "passive"))
      (node (ref "C74") (pin "1") (pinfunction "1_1") (pintype "passive"))
      (node (ref "C75") (pin "1") (pinfunction "1_1") (pintype "passive"))
      (node (ref "C76") (pin "1") (pinfunction "1_1") (pintype "passive"))
      (node (ref "C77") (pin "1") (pinfunction "1_1") (pintype "passive"))
      (node (ref "C78") (pin "1") (pinfunction "1_1") (pintype "passive"))
      (node (ref "C79") (pin "1") (pinfunction "1_1") (pintype "passive"))
      (node (ref "C80") (pin "1") (pinfunction "1_1") (pintype "passive"))
      (node (ref "C81") (pin "1") (pinfunction "1_1") (pintype "passive"))
      (node (ref "C82") (pin "1") (pinfunction "1_1") (pintype "passive"))
      (node (ref "IC1") (pin "AH30") (pinfunction "DIGPRVDD2_AH30") (pintype "power_in"))
      (node (ref "IC1") (pin "H32") (pinfunction "DIGPRVDD2_H32") (pintype "power_in"))
      (node (ref "IC1") (pin "T32") (pinfunction "DIGPRVDD2_T32") (pintype "power_in"))
      (node (ref "IC1") (pin "W31") (pinfunction "DIGPRPOC_W31") (pintype "power_in"))
      (node (ref "IC1") (pin "W33") (pinfunction "DIGPRVDD2_W33") (pintype "power_in"))
      (node (ref "R31") (pin "2") (pinfunction "2_2") (pintype "passive"))
    )
    (net (code "7") (name "Net-(IC1E-VDD18_BIAS)") (class "Default")
      (node (ref "C86") (pin "1") (pinfunction "1_1") (pintype "passive"))
      (node (ref "FR31") (pin "1") (pinfunction "1_1") (pintype "passive"))
      (node (ref "IC1") (pin "E17") (pinfunction "VDD18_BIAS_E17") (pintype "power_in"))
    )
    (net (code "8") (name "Net-(IC1E-VDD18_DIG)") (class "Default")
      (node (ref "C72") (pin "1") (pinfunction "1_1") (pintype "passive"))
      (node (ref "IC1") (pin "D24") (pinfunction "VDD18_DIG_D24") (pintype "power_in"))
      (node (ref "R30") (pin "1") (pinfunction "1_1") (pintype "passive"))
    )
    (net (code "9") (name "Net-(IC1E-VDD18_LDO_RX)") (class "Default")
      (node (ref "C89") (pin "1") (pinfunction "1_1") (pintype "passive"))
      (node (ref "FR28") (pin "2") (pinfunction "2_2") (pintype "passive"))
      (node (ref "IC1") (pin "AE3") (pinfunction "VDD18_TIA_RFE_AE3") (pintype "power_in"))
      (node (ref "IC1") (pin "AF4") (pinfunction "VDD18_LDO_RX_AF4") (pintype "power_in"))
    )
    (net (code "10") (name "Net-(IC1E-VDD18_LDO_TX)") (class "Default")
      (node (ref "C90") (pin "1") (pinfunction "1_1") (pintype "passive"))
      (node (ref "FR27") (pin "2") (pinfunction "2_2") (pintype "passive"))
      (node (ref "IC1") (pin "N1") (pinfunction "VDD18_LDO_TX_N1") (pintype "power_in"))
    )
    (net (code "11") (name "Net-(IC1E-VDD18_RXBUF)") (class "Default")
      (node (ref "C91") (pin "1") (pinfunction "1_1") (pintype "passive"))
      (node (ref "FR35") (pin "1") (pinfunction "1_1") (pintype "passive"))
      (node (ref "IC1") (pin "AM26") (pinfunction "VDD18_RXBUF_AM26") (pintype "power_in"))
    )
    (net (code "12") (name "Net-(IC1E-VDD18_SXR)") (class "Default")
      (node (ref "C88") (pin "1") (pinfunction "1_1") (pintype "passive"))
      (node (ref "FR29") (pin "1") (pinfunction "1_1") (pintype "passive"))
      (node (ref "IC1") (pin "AM18") (pinfunction "VDD18_SXR_AM18") (pintype "power_in"))
    )
    (net (code "13") (name "Net-(IC1E-VDD18_TRF)") (class "Default")
      (node (ref "C85") (pin "1") (pinfunction "1_1") (pintype "passive"))
      (node (ref "FR32") (pin "1") (pinfunction "1_1") (pintype "passive"))
      (node (ref "IC1") (pin "D16") (pinfunction "VDD18_TRF_D16") (pintype "power_in"))
    )
    (net (code "14") (name "Net-(IC1E-VDD18_TXBUF)") (class "Default")
      (node (ref "C92") (pin "1") (pinfunction "1_1") (pintype "passive"))
      (node (ref "FR34") (pin "2") (pinfunction "2_2") (pintype "passive"))
      (node (ref "IC1") (pin "H6") (pinfunction "VDD18_TXBUF_H6") (pintype "power_in"))
    )
    (net (code "15") (name "Net-(IC1E-VDD18_VCO_CGEN)") (class "Default")
      (node (ref "C84") (pin "1") (pinfunction "1_1") (pintype "passive"))
      (node (ref "FR33") (pin "1") (pinfunction "1_1") (pintype "passive"))
      (node (ref "IC1") (pin "E21") (pinfunction "VDD18_VCO_CGEN_E21") (pintype "power_in"))
    )
    (net (code "16") (name "Net-(IC1E-VDD18_VCO_SXR)") (class "Default")
      (node (ref "C87") (pin "1") (pinfunction "1_1") (pintype "passive"))
      (node (ref "FR30") (pin "1") (pinfunction "1_1") (pintype "passive"))
      (node (ref "IC1") (pin "AK22") (pinfunction "VDD18_VCO_SXR_AK22") (pintype "power_in"))
    )
    (net (code "17") (name "Net-(IC1E-VDD18_VCO_SXT)") (class "Default")
      (node (ref "C83") (pin "1") (pinfunction "1_1") (pintype "passive"))
      (node (ref "FR26") (pin "1") (pinfunction "1_1") (pintype "passive"))
      (node (ref "IC1") (pin "G3") (pinfunction "VDD18_VCO_SXT_G3") (pintype "power_in"))
    )
    (net (code "18") (name "Net-(IC1F-DVDD_CGEN)") (class "Default")
      (node (ref "C37") (pin "1") (pinfunction "1_1") (pintype "passive"))
      (node (ref "C38") (pin "1") (pinfunction "1_1") (pintype "passive"))
      (node (ref "C39") (pin "1") (pinfunction "1_1") (pintype "passive"))
      (node (ref "FR7") (pin "1") (pinfunction "1_1") (pintype "passive"))
      (node (ref "IC1") (pin "A17") (pinfunction "DVDD_CGEN_A17") (pintype "power_in"))
      (node (ref "IC1") (pin "C25") (pinfunction "VDD12_DIG_C25") (pintype "power_in"))
      (node (ref "IC1") (pin "F24") (pinfunction "VDD_SPI_BUF_F24") (pintype "power_in"))
    )
    (net (code "19") (name "Net-(IC1F-DVDD_SXR)") (class "Default")
      (node (ref "C41") (pin "1") (pinfunction "1_1") (pintype "passive"))
      (node (ref "FR5") (pin "1") (pinfunction "1_1") (pintype "passive"))
      (node (ref "IC1") (pin "AL21") (pinfunction "DVDD_SXR_AL21") (pintype "power_in"))
    )
    (net (code "20") (name "Net-(IC1F-DVDD_SXT)") (class "Default")
      (node (ref "C40") (pin "2") (pinfunction "2_2") (pintype "passive"))
      (node (ref "FR6") (pin "1") (pinfunction "1_1") (pintype "passive"))
      (node (ref "IC1") (pin "M4") (pinfunction "DVDD_SXT_M4") (pintype "power_in"))
    )
    (net (code "21") (name "Net-(IC1F-VDD12O_VCO_SXT)") (class "Default")
      (node (ref "C63") (pin "2") (pinfunction "2_2") (pintype "passive"))
      (node (ref "FR8") (pin "1") (pinfunction "1_1") (pintype "passive"))
      (node (ref "IC1") (pin "J5") (pinfunction "VDD12O_VCO_SXT_J5") (pintype "power_in"))
      (node (ref "IC1") (pin "K6") (pinfunction "VDD12_VCO_SXT_K6") (pintype "power_in"))
    )
    (net (code "22") (name "Net-(IC1F-VDD12_LNA_RFE)") (class "Default")
      (node (ref "C60") (pin "1") (pinfunction "1_1") (pintype "passive"))
      (node (ref "FR12") (pin "1") (pinfunction "1_1") (pintype "passive"))
      (node (ref "IC1") (pin "AG5") (pinfunction "VDD12_LNA_RFE_AG5") (pintype "power_in"))
    )
    (net (code "23") (name "Net-(IC1F-VDD12_RXBUF)") (class "Default")
      (node (ref "C56") (pin "1") (pinfunction "1_1") (pintype "passive"))
      (node (ref "IC1") (pin "AP26") (pinfunction "VDD12_RXBUF_AP26") (pintype "power_in"))
      (node (ref "R29") (pin "1") (pinfunction "1_1") (pintype "passive"))
    )
    (net (code "24") (name "Net-(IC1F-VDD12_TIA_RFE)") (class "Default")
      (node (ref "C61") (pin "2") (pinfunction "2_2") (pintype "passive"))
      (node (ref "FR11") (pin "1") (pinfunction "1_1") (pintype "passive"))
      (node (ref "IC1") (pin "AD6") (pinfunction "VDD12_TIA_RFE_AD6") (pintype "power_in"))
    )
    (net (code "25") (name "Net-(IC1F-VDD12_TXBUF)") (class "Default")
      (node (ref "C48") (pin "1") (pinfunction "1_1") (pintype "passive"))
      (node (ref "IC1") (pin "G5") (pinfunction "VDD12_TXBUF_G5") (pintype "power_in"))
      (node (ref "R28") (pin "1") (pinfunction "1_1") (pintype "passive"))
    )
    (net (code "26") (name "Net-(IC1F-VDD12_VCO_SXR)") (class "Default")
      (node (ref "C57") (pin "1") (pinfunction "1_1") (pintype "passive"))
      (node (ref "FR15") (pin "1") (pinfunction "1_1") (pintype "passive"))
      (node (ref "IC1") (pin "AN23") (pinfunction "VDD12_VCO_SXR_AN23") (pintype "power_in"))
    )
    (net (code "27") (name "Net-(IC1F-VDD14_LNA_RFE)") (class "Default")
      (node (ref "C68") (pin "1") (pinfunction "1_1") (pintype "passive"))
      (node (ref "C69") (pin "1") (pinfunction "1_1") (pintype "passive"))
      (node (ref "C70") (pin "1") (pinfunction "1_1") (pintype "passive"))
      (node (ref "FR24") (pin "1") (pinfunction "1_1") (pintype "passive"))
      (node (ref "IC1") (pin "AD4") (pinfunction "VDD14_RBB_AD4") (pintype "power_in"))
      (node (ref "IC1") (pin "AF2") (pinfunction "VDD14_TIA_RFE_AF2") (pintype "power_in"))
      (node (ref "IC1") (pin "AF6") (pinfunction "VDD14_LNA_RFE_AF6") (pintype "power_in"))
    )
    (net (code "28") (name "Net-(IC1F-VDD14_VCO_CGEN)") (class "Default")
      (node (ref "C66") (pin "1") (pinfunction "1_1") (pintype "passive"))
      (node (ref "C67") (pin "1") (pinfunction "1_1") (pintype "passive"))
      (node (ref "FR25") (pin "1") (pinfunction "1_1") (pintype "passive"))
      (node (ref "IC1") (pin "C21") (pinfunction "VDD14_VCO_CGEN_C21") (pintype "power_in"))
    )
    (net (code "29") (name "Net-(IC1F-VDDO_DIV_SXT)") (class "Default")
      (node (ref "C65") (pin "1") (pinfunction "1_1") (pintype "passive"))
      (node (ref "FR22") (pin "1") (pinfunction "1_1") (pintype "passive"))
      (node (ref "IC1") (pin "K2") (pinfunction "VDDO_DIV_SXT_K2") (pintype "power_in"))
      (node (ref "IC1") (pin "L5") (pinfunction "VDD_DIV_SXT_L5") (pintype "power_in"))
    )
    (net (code "30") (name "Net-(IC1F-VDDO_TLOBUF_TRF)") (class "Default")
      (node (ref "C50") (pin "1") (pinfunction "1_1") (pintype "passive"))
      (node (ref "FR21") (pin "1") (pinfunction "1_1") (pintype "passive"))
      (node (ref "IC1") (pin "D6") (pinfunction "VDDO_TLOBUF_TRF_D6") (pintype "power_in"))
      (node (ref "IC1") (pin "F8") (pinfunction "VDD_TLOBUF_TRF_F8") (pintype "power_in"))
    )
    (net (code "31") (name "Net-(IC1F-VDD_AFE)") (class "Default")
      (node (ref "C55") (pin "1") (pinfunction "1_1") (pintype "passive"))
      (node (ref "FR17") (pin "1") (pinfunction "1_1") (pintype "passive"))
      (node (ref "IC1") (pin "AJ25") (pinfunction "VDD_AFE_AJ25") (pintype "power_in"))
    )
    (net (code "32") (name "Net-(IC1F-VDD_CP_CGEN)") (class "Default")
      (node (ref "C54") (pin "2") (pinfunction "2_2") (pintype "passive"))
      (node (ref "FR18") (pin "1") (pinfunction "1_1") (pintype "passive"))
      (node (ref "IC1") (pin "F20") (pinfunction "VDD_CP_CGEN_F20") (pintype "power_in"))
    )
    (net (code "33") (name "Net-(IC1F-VDD_CP_SXR)") (class "Default")
      (node (ref "C59") (pin "1") (pinfunction "1_1") (pintype "passive"))
      (node (ref "FR13") (pin "1") (pinfunction "1_1") (pintype "passive"))
      (node (ref "IC1") (pin "AL19") (pinfunction "VDD_CP_SXR_AL19") (pintype "power_in"))
    )
    (net (code "34") (name "Net-(IC1F-VDD_CP_SXT)") (class "Default")
      (node (ref "C62") (pin "1") (pinfunction "1_1") (pintype "passive"))
      (node (ref "FR9") (pin "1") (pinfunction "1_1") (pintype "passive"))
      (node (ref "IC1") (pin "J3") (pinfunction "VDD_CP_SXT_J3") (pintype "power_in"))
    )
    (net (code "35") (name "Net-(IC1F-VDD_DIV_CGEN)") (class "Default")
      (node (ref "C52") (pin "1") (pinfunction "1_1") (pintype "passive"))
      (node (ref "C53") (pin "1") (pinfunction "1_1") (pintype "passive"))
      (node (ref "FR19") (pin "1") (pinfunction "1_1") (pintype "passive"))
      (node (ref "IC1") (pin "E19") (pinfunction "VDD_DIV_CGEN_E19") (pintype "power_in"))
    )
    (net (code "36") (name "Net-(IC1F-VDD_DIV_SXR)") (class "Default")
      (node (ref "C58") (pin "1") (pinfunction "1_1") (pintype "passive"))
      (node (ref "FR14") (pin "1") (pinfunction "1_1") (pintype "passive"))
      (node (ref "IC1") (pin "AM20") (pinfunction "VDD_DIV_SXR_AM20") (pintype "power_in"))
    )
    (net (code "37") (name "Net-(IC1F-VDD_MXLOBUF_RFE)") (class "Default")
      (node (ref "C71") (pin "1") (pinfunction "1_1") (pintype "passive"))
      (node (ref "FR23") (pin "1") (pinfunction "1_1") (pintype "passive"))
      (node (ref "IC1") (pin "AN17") (pinfunction "VDD_MXLOBUF_RFE_AN17") (pintype "power_in"))
    )
    (net (code "38") (name "Net-(IC1F-VDD_TBB)") (class "Default")
      (node (ref "C49") (pin "1") (pinfunction "1_1") (pintype "passive"))
      (node (ref "FR10") (pin "1") (pinfunction "1_1") (pintype "passive"))
      (node (ref "FR55") (pin "1") (pinfunction "1_1") (pintype "passive"))
      (node (ref "IC1") (pin "P4") (pinfunction "VDD_TBB_P4") (pintype "power_in"))
    )
    (net (code "39") (name "Net-(IC1F-VDD_TPAD_TRF)") (class "Default")
      (node (ref "C51") (pin "1") (pinfunction "1_1") (pintype "passive"))
      (node (ref "FR20") (pin "1") (pinfunction "1_1") (pintype "passive"))
      (node (ref "IC1") (pin "B16") (pinfunction "VDD_TPAD_TRF_B16") (pintype "power_in"))
    )
    (net (code "40") (name "VCC1P4_LMS") (class "Default")
      (node (ref "FR10") (pin "2") (pinfunction "2_2") (pintype "passive"))
      (node (ref "FR22") (pin "2") (pinfunction "2_2") (pintype "passive"))
      (node (ref "FR23") (pin "2") (pinfunction "2_2") (pintype "passive"))
      (node (ref "FR24") (pin "2") (pinfunction "2_2") (pintype "passive"))
      (node (ref "FR25") (pin "2") (pinfunction "2_2") (pintype "passive"))
    )
    (net (code "41") (name "VCC1P8_LMS") (class "Default")
      (node (ref "FR26") (pin "2") (pinfunction "2_2") (pintype "passive"))
      (node (ref "FR27") (pin "1") (pinfunction "1_1") (pintype "passive"))
      (node (ref "FR28") (pin "1") (pinfunction "1_1") (pintype "passive"))
      (node (ref "FR29") (pin "2") (pinfunction "2_2") (pintype "passive"))
      (node (ref "FR30") (pin "2") (pinfunction "2_2") (pintype "passive"))
      (node (ref "FR31") (pin "2") (pinfunction "2_2") (pintype "passive"))
      (node (ref "FR32") (pin "2") (pinfunction "2_2") (pintype "passive"))
      (node (ref "FR33") (pin "2") (pinfunction "2_2") (pintype "passive"))
      (node (ref "R30") (pin "2") (pinfunction "2_2") (pintype "passive"))
      (node (ref "R32") (pin "2") (pinfunction "2_2") (pintype "passive"))
      (node (ref "R33") (pin "1") (pinfunction "1_1") (pintype "passive"))
    )
    (net (code "42") (name "VCC1P25_LMS") (class "Default")
      (node (ref "FR11") (pin "2") (pinfunction "2_2") (pintype "passive"))
      (node (ref "FR12") (pin "2") (pinfunction "2_2") (pintype "passive"))
      (node (ref "FR13") (pin "2") (pinfunction "2_2") (pintype "passive"))
      (node (ref "FR14") (pin "2") (pinfunction "2_2") (pintype "passive"))
      (node (ref "FR15") (pin "2") (pinfunction "2_2") (pintype "passive"))
      (node (ref "FR16") (pin "2") (pinfunction "2_2") (pintype "passive"))
      (node (ref "FR17") (pin "2") (pinfunction "2_2") (pintype "passive"))
      (node (ref "FR18") (pin "2") (pinfunction "2_2") (pintype "passive"))
      (node (ref "FR19") (pin "2") (pinfunction "2_2") (pintype "passive"))
      (node (ref "FR20") (pin "2") (pinfunction "2_2") (pintype "passive"))
      (node (ref "FR21") (pin "2") (pinfunction "2_2") (pintype "passive"))
      (node (ref "FR5") (pin "2") (pinfunction "2_2") (pintype "passive"))
      (node (ref "FR55") (pin "2") (pinfunction "2_2") (pintype "passive"))
      (node (ref "FR6") (pin "2") (pinfunction "2_2") (pintype "passive"))
      (node (ref "FR7") (pin "2") (pinfunction "2_2") (pintype "passive"))
      (node (ref "FR8") (pin "2") (pinfunction "2_2") (pintype "passive"))
      (node (ref "FR9") (pin "2") (pinfunction "2_2") (pintype "passive"))
      (node (ref "R27") (pin "1") (pinfunction "1_1") (pintype "passive"))
    )
    (net (code "43") (name "VDIO_LMS") (class "Default")
      (node (ref "R31") (pin "1") (pinfunction "1_1") (pintype "passive"))
    )
  )
)
